# MHI_Board.net
KiCad netlist of a schematic drawn in Altium Designer
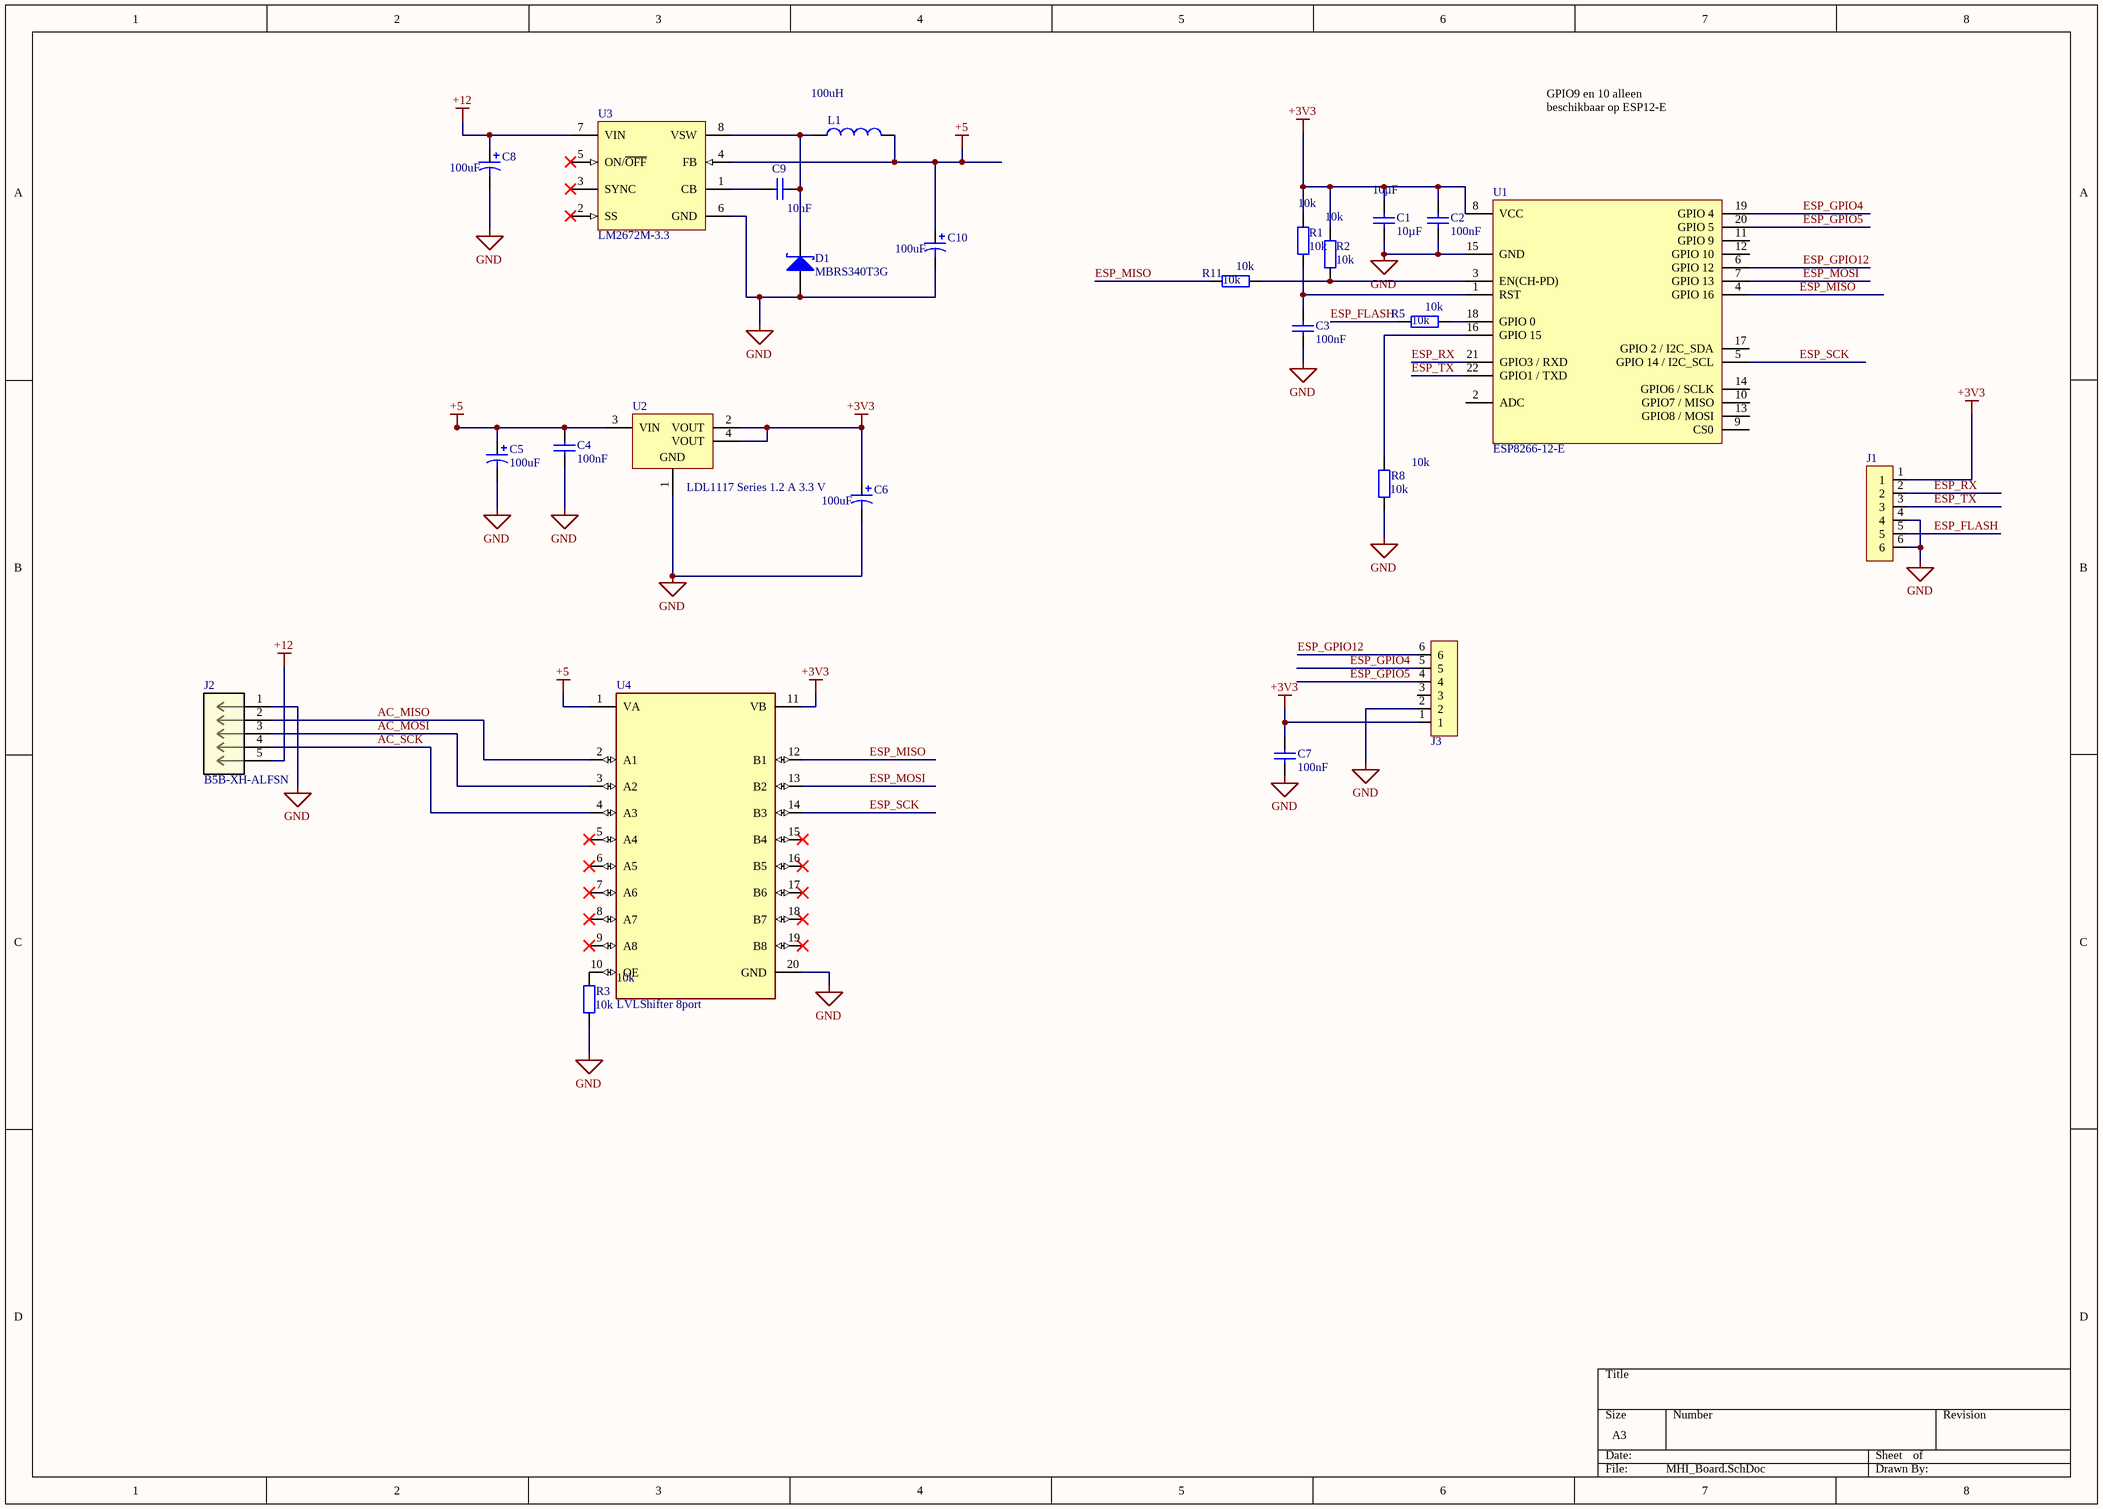
[diagram p0: MHI_Board.SchDoc]

(export (version "E")
  (design (tool "Eeschema 10.0.6"))
  (components
    (comp (ref "C1")
      (value "10µF")
      (footprint "CAPC2013X145X50NL20T25")
      (description "Cap Ceramic 10uF 6.3V X5R 20% SMD 0805 85C Plastic T/R")
      (fields (field (name "CAPACITANCE") "10µF"))
      (libsource (lib "CommunityVault") (part "CMP-158161-2"))
    )
    (comp (ref "C2")
      (value "100nF")
      (footprint "CAPC1608X90X35ML10T15")
      (description "CAP CER 0.1UF 50V 10% X7R 0603")
      (libsource (lib "CommunityVault") (part "CMP-119667-3"))
    )
    (comp (ref "C3")
      (value "100nF")
      (footprint "CAPC1608X90X35ML10T15")
      (description "CAP CER 0.1UF 50V 10% X7R 0603")
      (libsource (lib "CommunityVault") (part "CMP-119667-3"))
    )
    (comp (ref "C4")
      (value "100nF")
      (footprint "CAPC1608X90X35ML10T15")
      (description "CAP CER 0.1UF 50V 10% X7R 0603")
      (libsource (lib "CommunityVault") (part "CMP-119667-3"))
    )
    (comp (ref "C5")
      (value "Panasonic EEE-FT1E101AP")
      (footprint "ELECTRO-SMD-D-5.6MM")
      (description "Capacitor Alum Elec, 100uf, 20%, 25v, Capacitor Alum Elec, 100uf, 20%, 25v, Smd, Full Reel")
      (fields (field (name "CAPACITANCE") "100uF") (field (name "MANUFACTURER PART NUMBER") "EEE-FT1E101AP"))
      (libsource (lib "HV-Board") (part "CMP-848b4cb3b4f95b4c-3"))
    )
    (comp (ref "C6")
      (value "Panasonic EEE-FT1E101AP")
      (footprint "ELECTRO-SMD-D-5.6MM")
      (description "Capacitor Alum Elec, 100uf, 20%, 25v, Capacitor Alum Elec, 100uf, 20%, 25v, Smd, Full Reel")
      (fields (field (name "CAPACITANCE") "100uF") (field (name "MANUFACTURER PART NUMBER") "EEE-FT1E101AP"))
      (libsource (lib "HV-Board") (part "CMP-848b4cb3b4f95b4c-3"))
    )
    (comp (ref "C7")
      (value "100nF")
      (footprint "CAPC1608X90X35ML10T15")
      (description "CAP CER 0.1UF 50V 10% X7R 0603")
      (libsource (lib "CommunityVault") (part "CMP-119667-3"))
    )
    (comp (ref "C8")
      (value "Panasonic EEE-FT1E101AP")
      (footprint "ELECTRO-SMD-D-5.6MM")
      (description "Capacitor Alum Elec, 100uf, 20%, 25v, Capacitor Alum Elec, 100uf, 20%, 25v, Smd, Full Reel")
      (fields (field (name "CAPACITANCE") "100uF") (field (name "MANUFACTURER PART NUMBER") "EEE-FT1E101AP"))
      (libsource (lib "HV-Board") (part "CMP-848b4cb3b4f95b4c-3"))
    )
    (comp (ref "C9")
      (value "AVX Interconnect / Elco 08051C103KAZ2A")
      (footprint "CAPC2013X94X50NL20T25")
      (description "CAP CER 10000PF 100V X7R 0805")
      (fields (field (name "MANUFACTURER PART NUMBER") "08051C103KAZ2A") (field (name "CAPACITANCE") "10nF"))
      (libsource (lib "HV-Board") (part "CMP-126385-2"))
    )
    (comp (ref "C10")
      (value "Panasonic EEE-FT1E101AP")
      (footprint "ELECTRO-SMD-D-5.6MM")
      (description "Capacitor Alum Elec, 100uf, 20%, 25v, Capacitor Alum Elec, 100uf, 20%, 25v, Smd, Full Reel")
      (fields (field (name "CAPACITANCE") "100uF") (field (name "MANUFACTURER PART NUMBER") "EEE-FT1E101AP"))
      (libsource (lib "HV-Board") (part "CMP-848b4cb3b4f95b4c-3"))
    )
    (comp (ref "D1")
      (value "ON Semiconductor MBRS340T-3G")
      (footprint "ONSC-SMC_AP419")
      (description "ON Semiconductor")
      (fields (field (name "MANUFACTURER PART NUMBER") "MBRS340T3G"))
      (libsource (lib "HV-Board") (part "CMP-13076272-7"))
    )
    (comp (ref "J1")
      (value "TE Connectivity / AMP 5-146280-6")
      (footprint "PCB-inh0upq8uddmt7lk8pts-1")
      (description "AMPMODU 6 Position 2.54 mm Through Hole Single Row Straight Breakaway Header")
      (fields (field (name "MANUFACTURER PART NUMBER") "5-146280-6"))
      (libsource (lib "") (part "CMP-5a24914ca12285e3-2_1"))
    )
    (comp (ref "J2")
      (value "B5B-XH-ALFSN")
      (footprint "CONN_B5B-XH-ALFSN_JST")
      (description "No Description Available")
      (libsource (lib "MHI_Board") (part "B5B-XH-ALFSN"))
    )
    (comp (ref "J3")
      (value "TE Connectivity / AMP 5-146280-6")
      (footprint "PCB-inh0upq8uddmt7lk8pts-1")
      (description "AMPMODU 6 Position 2.54 mm Through Hole Single Row Straight Breakaway Header")
      (fields (field (name "MANUFACTURER PART NUMBER") "5-146280-6"))
      (libsource (lib "CommunityVault") (part "CMP-5a24914ca12285e3-2"))
    )
    (comp (ref "L1")
      (value "TDK SLF7045T-101MR50-PF")
      (footprint "PCB-910519-1")
      (description "INDUCTOR SHIELD PWR 100UH 7045")
      (fields
        (field (name "MANUFACTURER PART NUMBER") "SLF7045T-101MR50-PF")
        (field (name "INDUCTANCE") "100uH")
      )
      (libsource (lib "HV-Board") (part "CMP-910519-3"))
    )
    (comp (ref "R1")
      (value "10k")
      (footprint "RESC1609X50X30ML10T20")
      (description "Resistor; Thick Film; Res 10 Kilohms; Pwr-Rtg 0.1 W; Tol 1%; SMT; 0603")
      (fields (field (name "MANUFACTURER PART NUMBER") "CRG0603F10K") (field (name "RESISTANCE") "10k"))
      (libsource (lib "") (part "CMP-584891b72cc4878f-1_1"))
    )
    (comp (ref "R2")
      (value "10k")
      (footprint "RESC1609X50X30ML10T20")
      (description "Resistor; Thick Film; Res 10 Kilohms; Pwr-Rtg 0.1 W; Tol 1%; SMT; 0603")
      (fields (field (name "MANUFACTURER PART NUMBER") "CRG0603F10K") (field (name "RESISTANCE") "10k"))
      (libsource (lib "") (part "CMP-584891b72cc4878f-1_1"))
    )
    (comp (ref "R3")
      (value "10k")
      (footprint "RESC1609X50X30ML10T20")
      (description "Resistor; Thick Film; Res 10 Kilohms; Pwr-Rtg 0.1 W; Tol 1%; SMT; 0603")
      (fields (field (name "MANUFACTURER PART NUMBER") "CRG0603F10K") (field (name "RESISTANCE") "10k"))
      (libsource (lib "HV-Board") (part "CMP-584891b72cc4878f-1"))
    )
    (comp (ref "R5")
      (value "10k")
      (footprint "RESC1609X50X30ML10T20")
      (description "Resistor; Thick Film; Res 10 Kilohms; Pwr-Rtg 0.1 W; Tol 1%; SMT; 0603")
      (fields (field (name "MANUFACTURER PART NUMBER") "CRG0603F10K") (field (name "RESISTANCE") "10k"))
      (libsource (lib "CommunityVault") (part "CMP-584891b72cc4878f-1"))
    )
    (comp (ref "R8")
      (value "10k")
      (footprint "RESC1609X50X30ML10T20")
      (description "Resistor; Thick Film; Res 10 Kilohms; Pwr-Rtg 0.1 W; Tol 1%; SMT; 0603")
      (fields (field (name "MANUFACTURER PART NUMBER") "CRG0603F10K") (field (name "RESISTANCE") "10k"))
      (libsource (lib "") (part "CMP-584891b72cc4878f-1_1"))
    )
    (comp (ref "R11")
      (value "10k")
      (footprint "RESC1609X50X30ML10T20")
      (description "Resistor; Thick Film; Res 10 Kilohms; Pwr-Rtg 0.1 W; Tol 1%; SMT; 0603")
      (fields (field (name "MANUFACTURER PART NUMBER") "CRG0603F10K") (field (name "RESISTANCE") "10k"))
      (libsource (lib "CommunityVault") (part "CMP-584891b72cc4878f-1"))
    )
    (comp (ref "U1")
      (value "ESP8266-12-E")
      (footprint "2491")
      (description "ESP8266 SMT MODULE")
      (fields (field (name "MANUFACTURER PART NUMBER") "2491"))
      (libsource (lib "MHI_Board") (part "SYM-f2f4381d21f22d33-13"))
    )
    (comp (ref "U2")
      (value "LDL1117 Series 1.2 A 3.3 V")
      (footprint "PCB-elchkyvpbzx92dsq0s9t-1")
      (description "High PSRR LDO Linear Voltage Regulator-SOT-223")
      (libsource (lib "CommunityVault") (part "CMP-9f2a52c1ee8f40ed-1"))
    )
    (comp (ref "U3")
      (value "LM2672M-3.3")
      (footprint "M08A_M")
      (libsource (lib "HV-Board") (part "CMP-0069-00649-3"))
    )
    (comp (ref "U4")
      (value "LVLShifter 8port")
      (footprint "FP-N20A-W")
      (description "LevelShifter, PDIP20")
      (fields
        (field (name "MANUFACTURER") "ON Semiconductor / Fairchild")
        (field (name "MANUFACTURER PART NUMBER") "MM74HC688N")
      )
      (libsource (lib "MHI_Board") (part "CMP-00278-13160021-1"))
    )
  )
  (nets
    (net (code "1") (name "+3V3") (class "Default")
      (node (ref "C1") (pin "2") (pinfunction "2_2") (pintype "passive"))
      (node (ref "C2") (pin "2") (pinfunction "2_2") (pintype "passive"))
      (node (ref "C6") (pin "1") (pinfunction "+_1") (pintype "passive"))
      (node (ref "C7") (pin "2") (pinfunction "2_2") (pintype "passive"))
      (node (ref "J1") (pin "1") (pinfunction "1_1") (pintype "passive"))
      (node (ref "J3") (pin "1") (pinfunction "1_1") (pintype "passive"))
      (node (ref "R1") (pin "2") (pinfunction "2_2") (pintype "passive"))
      (node (ref "R2") (pin "2") (pinfunction "2_2") (pintype "passive"))
      (node (ref "U1") (pin "8") (pinfunction "VCC_8") (pintype "power_in"))
      (node (ref "U2") (pin "2") (pinfunction "VOUT_2") (pintype "power_in"))
      (node (ref "U2") (pin "4") (pinfunction "VOUT_4") (pintype "power_in"))
      (node (ref "U4") (pin "11") (pinfunction "VB_11") (pintype "power_in"))
    )
    (net (code "2") (name "+5") (class "Default")
      (node (ref "C10") (pin "1") (pinfunction "+_1") (pintype "passive"))
      (node (ref "C4") (pin "2") (pinfunction "2_2") (pintype "passive"))
      (node (ref "C5") (pin "1") (pinfunction "+_1") (pintype "passive"))
      (node (ref "L1") (pin "2") (pinfunction "2_2") (pintype "passive"))
      (node (ref "U2") (pin "3") (pinfunction "VIN_3") (pintype "power_in"))
      (node (ref "U3") (pin "4") (pinfunction "FB_4") (pintype "input"))
      (node (ref "U4") (pin "1") (pinfunction "VA_1") (pintype "power_in"))
    )
    (net (code "3") (name "+12") (class "Default")
      (node (ref "C8") (pin "1") (pinfunction "+_1") (pintype "passive"))
      (node (ref "J2") (pin "5") (pinfunction "5_5") (pintype "passive"))
      (node (ref "U3") (pin "7") (pinfunction "VIN_7") (pintype "power_in"))
    )
    (net (code "4") (name "/AC_MISO") (class "Default")
      (node (ref "J2") (pin "2") (pinfunction "2_2") (pintype "passive"))
      (node (ref "U4") (pin "2") (pinfunction "A1_2") (pintype "bidirectional"))
    )
    (net (code "5") (name "/AC_MOSI") (class "Default")
      (node (ref "J2") (pin "3") (pinfunction "3_3") (pintype "passive"))
      (node (ref "U4") (pin "3") (pinfunction "A2_3") (pintype "bidirectional"))
    )
    (net (code "6") (name "/AC_SCK") (class "Default")
      (node (ref "J2") (pin "4") (pinfunction "4_4") (pintype "passive"))
      (node (ref "U4") (pin "4") (pinfunction "A3_4") (pintype "bidirectional"))
    )
    (net (code "7") (name "/ESP_FLASH") (class "Default")
      (node (ref "J1") (pin "5") (pinfunction "5_5") (pintype "passive"))
      (node (ref "R5") (pin "2") (pinfunction "2_2") (pintype "passive"))
    )
    (net (code "8") (name "/ESP_GPIO4") (class "Default")
      (node (ref "J3") (pin "5") (pinfunction "5_5") (pintype "passive"))
      (node (ref "U1") (pin "19") (pinfunction "GPIO_4_19") (pintype "passive"))
    )
    (net (code "9") (name "/ESP_GPIO5") (class "Default")
      (node (ref "J3") (pin "4") (pinfunction "4_4") (pintype "passive"))
      (node (ref "U1") (pin "20") (pinfunction "GPIO_5_20") (pintype "passive"))
    )
    (net (code "10") (name "/ESP_GPIO12") (class "Default")
      (node (ref "J3") (pin "6") (pinfunction "6_6") (pintype "passive"))
      (node (ref "U1") (pin "6") (pinfunction "GPIO_12_6") (pintype "passive"))
    )
    (net (code "11") (name "/ESP_MISO") (class "Default")
      (node (ref "R11") (pin "2") (pinfunction "2_2") (pintype "passive"))
      (node (ref "U1") (pin "4") (pinfunction "GPIO_16_4") (pintype "passive"))
      (node (ref "U4") (pin "12") (pinfunction "B1_12") (pintype "bidirectional"))
    )
    (net (code "12") (name "/ESP_MOSI") (class "Default")
      (node (ref "U1") (pin "7") (pinfunction "GPIO_13_7") (pintype "passive"))
      (node (ref "U4") (pin "13") (pinfunction "B2_13") (pintype "bidirectional"))
    )
    (net (code "13") (name "/ESP_RX") (class "Default")
      (node (ref "J1") (pin "2") (pinfunction "2_2") (pintype "passive"))
      (node (ref "U1") (pin "21") (pinfunction "GPIO3_/_RXD_21") (pintype "passive"))
    )
    (net (code "14") (name "/ESP_SCK") (class "Default")
      (node (ref "U1") (pin "5") (pinfunction "GPIO_14_/_I2C_SCL_5") (pintype "passive"))
      (node (ref "U4") (pin "14") (pinfunction "B3_14") (pintype "bidirectional"))
    )
    (net (code "15") (name "/ESP_TX") (class "Default")
      (node (ref "J1") (pin "3") (pinfunction "3_3") (pintype "passive"))
      (node (ref "U1") (pin "22") (pinfunction "GPIO1_/_TXD_22") (pintype "passive"))
    )
    (net (code "16") (name "GND") (class "Default")
      (node (ref "C1") (pin "1") (pinfunction "1_1") (pintype "passive"))
      (node (ref "C10") (pin "2") (pinfunction "-_2") (pintype "passive"))
      (node (ref "C2") (pin "1") (pinfunction "1_1") (pintype "passive"))
      (node (ref "C3") (pin "1") (pinfunction "1_1") (pintype "passive"))
      (node (ref "C4") (pin "1") (pinfunction "1_1") (pintype "passive"))
      (node (ref "C5") (pin "2") (pinfunction "-_2") (pintype "passive"))
      (node (ref "C6") (pin "2") (pinfunction "-_2") (pintype "passive"))
      (node (ref "C7") (pin "1") (pinfunction "1_1") (pintype "passive"))
      (node (ref "C8") (pin "2") (pinfunction "-_2") (pintype "passive"))
      (node (ref "D1") (pin "2") (pinfunction "A_2") (pintype "passive"))
      (node (ref "J1") (pin "4") (pinfunction "4_4") (pintype "passive"))
      (node (ref "J1") (pin "6") (pinfunction "6_6") (pintype "passive"))
      (node (ref "J2") (pin "1") (pinfunction "1_1") (pintype "passive"))
      (node (ref "J3") (pin "2") (pinfunction "2_2") (pintype "passive"))
      (node (ref "R3") (pin "1") (pinfunction "1_1") (pintype "passive"))
      (node (ref "R8") (pin "1") (pinfunction "1_1") (pintype "passive"))
      (node (ref "U1") (pin "15") (pinfunction "GND_15") (pintype "passive"))
      (node (ref "U2") (pin "1") (pinfunction "GND_1") (pintype "power_in"))
      (node (ref "U3") (pin "6") (pinfunction "GND_6") (pintype "power_in"))
      (node (ref "U4") (pin "20") (pinfunction "GND_20") (pintype "power_in"))
    )
    (net (code "17") (name "Net-(D1-C)") (class "Default")
      (node (ref "C9") (pin "2") (pinfunction "2_2") (pintype "passive"))
      (node (ref "D1") (pin "1") (pinfunction "C_1") (pintype "passive"))
      (node (ref "L1") (pin "1") (pinfunction "1_1") (pintype "passive"))
      (node (ref "U3") (pin "8") (pinfunction "VSW_8") (pintype "power_in"))
    )
    (net (code "18") (name "Net-(U1-EN(CH-PD))") (class "Default")
      (node (ref "R11") (pin "1") (pinfunction "1_1") (pintype "passive"))
      (node (ref "R2") (pin "1") (pinfunction "1_1") (pintype "passive"))
      (node (ref "U1") (pin "3") (pinfunction "EN(CH-PD)_3") (pintype "passive"))
    )
    (net (code "19") (name "Net-(U1-GPIO_0)") (class "Default")
      (node (ref "R5") (pin "1") (pinfunction "1_1") (pintype "passive"))
      (node (ref "U1") (pin "18") (pinfunction "GPIO_0_18") (pintype "passive"))
    )
    (net (code "20") (name "Net-(U1-GPIO_15)") (class "Default")
      (node (ref "R8") (pin "2") (pinfunction "2_2") (pintype "passive"))
      (node (ref "U1") (pin "16") (pinfunction "GPIO_15_16") (pintype "passive"))
    )
    (net (code "21") (name "Net-(U1-RST)") (class "Default")
      (node (ref "C3") (pin "2") (pinfunction "2_2") (pintype "passive"))
      (node (ref "R1") (pin "1") (pinfunction "1_1") (pintype "passive"))
      (node (ref "U1") (pin "1") (pinfunction "RST_1") (pintype "passive"))
    )
    (net (code "22") (name "Net-(U3-CB)") (class "Default")
      (node (ref "C9") (pin "1") (pinfunction "1_1") (pintype "passive"))
      (node (ref "U3") (pin "1") (pinfunction "CB_1") (pintype "passive"))
    )
    (net (code "23") (name "Net-(U4-OE)") (class "Default")
      (node (ref "R3") (pin "2") (pinfunction "2_2") (pintype "passive"))
      (node (ref "U4") (pin "10") (pinfunction "OE_10") (pintype "bidirectional"))
    )
    (net (code "24") (name "unconnected-(J3-Pad3)") (class "Default")
      (node (ref "J3") (pin "3") (pinfunction "3_3") (pintype "passive"))
    )
    (net (code "25") (name "unconnected-(U1-ADC-Pad2)") (class "Default")
      (node (ref "U1") (pin "2") (pinfunction "ADC_2") (pintype "passive"))
    )
    (net (code "26") (name "unconnected-(U1-CS0-Pad9)") (class "Default")
      (node (ref "U1") (pin "9") (pinfunction "CS0_9") (pintype "passive"))
    )
    (net (code "27") (name "unconnected-(U1-GPIO6_{slash}_SCLK-Pad14)") (class "Default")
      (node (ref "U1") (pin "14") (pinfunction "GPIO6_/_SCLK_14") (pintype "passive"))
    )
    (net (code "28") (name "unconnected-(U1-GPIO7_{slash}_MISO-Pad10)") (class "Default")
      (node (ref "U1") (pin "10") (pinfunction "GPIO7_/_MISO_10") (pintype "passive"))
    )
    (net (code "29") (name "unconnected-(U1-GPIO8_{slash}_MOSI-Pad13)") (class "Default")
      (node (ref "U1") (pin "13") (pinfunction "GPIO8_/_MOSI_13") (pintype "passive"))
    )
    (net (code "30") (name "unconnected-(U1-GPIO_2_{slash}_I2C_SDA-Pad17)") (class "Default")
      (node (ref "U1") (pin "17") (pinfunction "GPIO_2_/_I2C_SDA_17") (pintype "passive"))
    )
    (net (code "31") (name "unconnected-(U1-GPIO_9-Pad11)") (class "Default")
      (node (ref "U1") (pin "11") (pinfunction "GPIO_9_11") (pintype "passive"))
    )
    (net (code "32") (name "unconnected-(U1-GPIO_10-Pad12)") (class "Default")
      (node (ref "U1") (pin "12") (pinfunction "GPIO_10_12") (pintype "passive"))
    )
    (net (code "33") (name "unconnected-(U3-ON{slash}~{OFF}-Pad5)") (class "Default")
      (node (ref "U3") (pin "5") (pinfunction "ON/~{OFF}_5") (pintype "input+no_connect"))
    )
    (net (code "34") (name "unconnected-(U3-SS-Pad2)") (class "Default")
      (node (ref "U3") (pin "2") (pinfunction "SS_2") (pintype "input+no_connect"))
    )
    (net (code "35") (name "unconnected-(U3-SYNC-Pad3)") (class "Default")
      (node (ref "U3") (pin "3") (pinfunction "SYNC_3") (pintype "passive+no_connect"))
    )
    (net (code "36") (name "unconnected-(U4-A4-Pad5)") (class "Default")
      (node (ref "U4") (pin "5") (pinfunction "A4_5") (pintype "bidirectional+no_connect"))
    )
    (net (code "37") (name "unconnected-(U4-A5-Pad6)") (class "Default")
      (node (ref "U4") (pin "6") (pinfunction "A5_6") (pintype "bidirectional+no_connect"))
    )
    (net (code "38") (name "unconnected-(U4-A6-Pad7)") (class "Default")
      (node (ref "U4") (pin "7") (pinfunction "A6_7") (pintype "bidirectional+no_connect"))
    )
    (net (code "39") (name "unconnected-(U4-A7-Pad8)") (class "Default")
      (node (ref "U4") (pin "8") (pinfunction "A7_8") (pintype "bidirectional+no_connect"))
    )
    (net (code "40") (name "unconnected-(U4-A8-Pad9)") (class "Default")
      (node (ref "U4") (pin "9") (pinfunction "A8_9") (pintype "bidirectional+no_connect"))
    )
    (net (code "41") (name "unconnected-(U4-B4-Pad15)") (class "Default")
      (node (ref "U4") (pin "15") (pinfunction "B4_15") (pintype "bidirectional+no_connect"))
    )
    (net (code "42") (name "unconnected-(U4-B5-Pad16)") (class "Default")
      (node (ref "U4") (pin "16") (pinfunction "B5_16") (pintype "bidirectional+no_connect"))
    )
    (net (code "43") (name "unconnected-(U4-B6-Pad17)") (class "Default")
      (node (ref "U4") (pin "17") (pinfunction "B6_17") (pintype "bidirectional+no_connect"))
    )
    (net (code "44") (name "unconnected-(U4-B7-Pad18)") (class "Default")
      (node (ref "U4") (pin "18") (pinfunction "B7_18") (pintype "bidirectional+no_connect"))
    )
    (net (code "45") (name "unconnected-(U4-B8-Pad19)") (class "Default")
      (node (ref "U4") (pin "19") (pinfunction "B8_19") (pintype "bidirectional+no_connect"))
    )
  )
)
